# LED_V2_0.net
KiCad netlist of a schematic drawn in Altium Designer
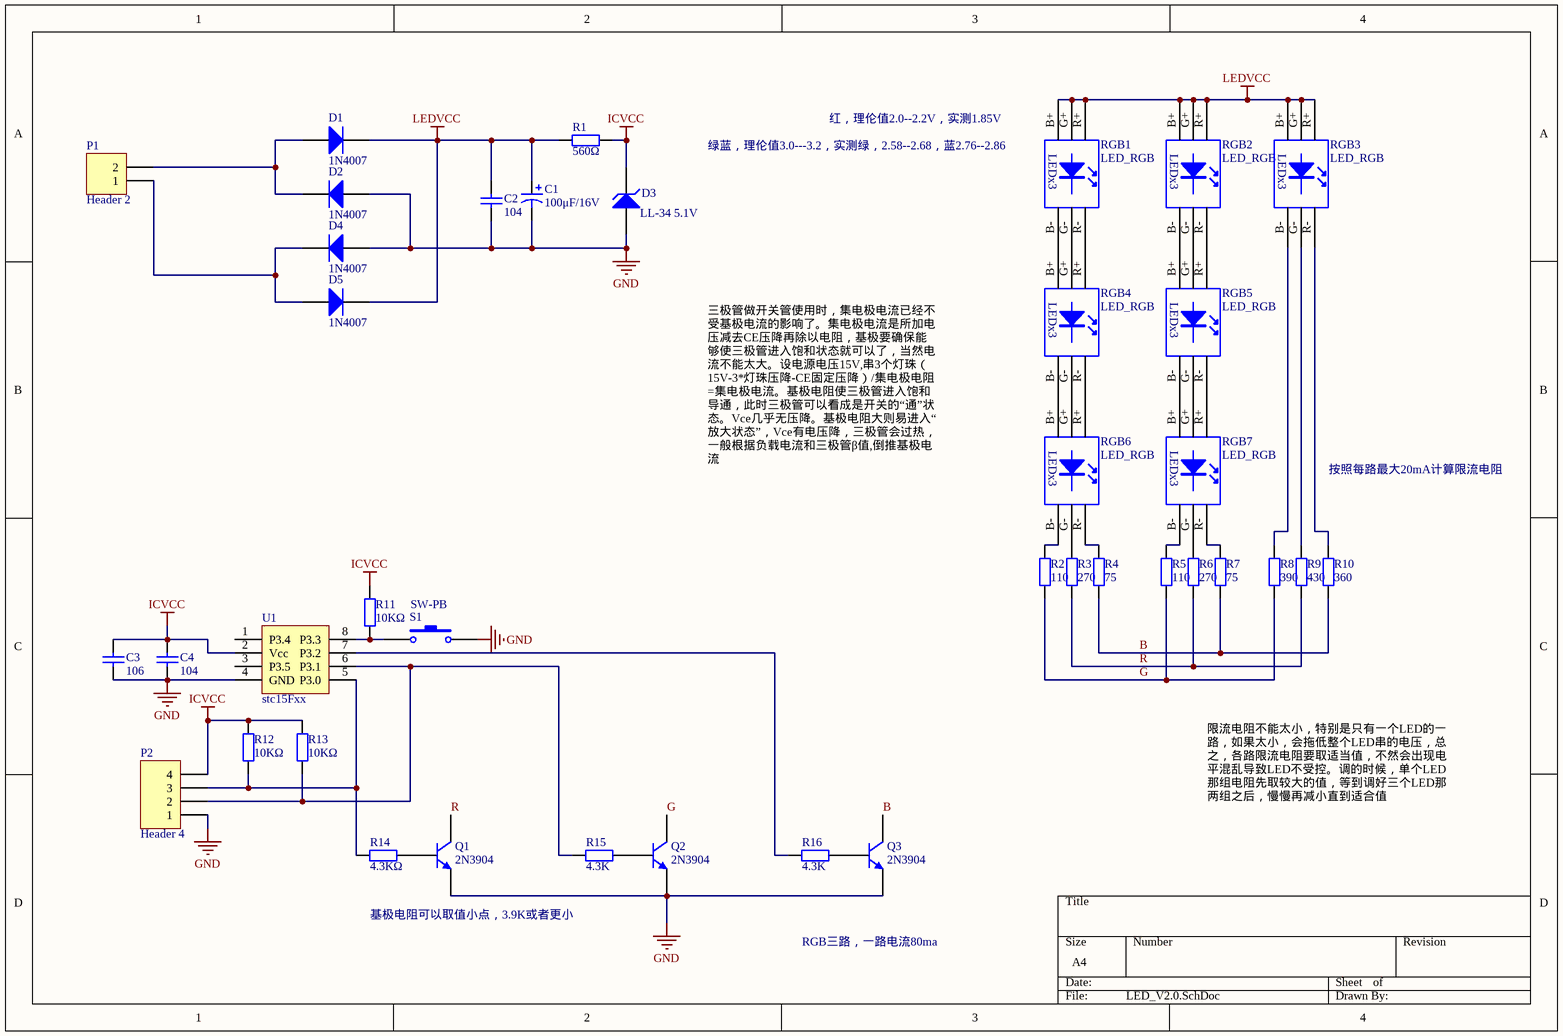
[diagram p0: LED_V2.0.SchDoc]

(export (version "E")
  (design (tool "Eeschema 10.0.6"))
  (components
    (comp (ref "C1")
      (value "100μF/16V")
      (footprint "CAP_D5")
      (description "Polarized Capacitor (Surface Mount)")
      (fields (field (name "PUBLISHER") "Altium Limited"))
      (libsource (lib "Miscellaneous Devices") (part "Cap Pol3"))
    )
    (comp (ref "C2")
      (value "104")
      (footprint "0805")
      (description "Capacitor")
      (fields (field (name "PUBLISHER") "Altium Limited"))
      (libsource (lib "Miscellaneous Devices") (part "Cap"))
    )
    (comp (ref "C3")
      (value "106")
      (footprint "0805")
      (description "Capacitor")
      (fields (field (name "PUBLISHER") "Altium Limited"))
      (libsource (lib "Miscellaneous Devices") (part "Cap"))
    )
    (comp (ref "C4")
      (value "104")
      (footprint "0805")
      (description "Capacitor")
      (fields (field (name "PUBLISHER") "Altium Limited"))
      (libsource (lib "Miscellaneous Devices") (part "Cap"))
    )
    (comp (ref "D1")
      (value "1N4007")
      (footprint "SMB_diode")
      (description "1 Amp General Purpose Rectifier")
      (fields (field (name "PUBLISHER") "Altium Limited"))
      (libsource (lib "Miscellaneous Devices") (part "Diode 1N4007"))
    )
    (comp (ref "D2")
      (value "1N4007")
      (footprint "SMB_diode")
      (description "1 Amp General Purpose Rectifier")
      (fields (field (name "PUBLISHER") "Altium Limited"))
      (libsource (lib "Miscellaneous Devices") (part "Diode 1N4007"))
    )
    (comp (ref "D3")
      (value "LL-34 5.1V")
      (footprint "SMB_diode")
      (description "Zener Diode")
      (fields (field (name "PUBLISHER") "Altium Limited"))
      (libsource (lib "Miscellaneous Devices") (part "D Zener"))
    )
    (comp (ref "D4")
      (value "1N4007")
      (footprint "SMB_diode")
      (description "1 Amp General Purpose Rectifier")
      (fields (field (name "PUBLISHER") "Altium Limited"))
      (libsource (lib "Miscellaneous Devices") (part "Diode 1N4007"))
    )
    (comp (ref "D5")
      (value "1N4007")
      (footprint "SMB_diode")
      (description "1 Amp General Purpose Rectifier")
      (fields (field (name "PUBLISHER") "Altium Limited"))
      (libsource (lib "Miscellaneous Devices") (part "Diode 1N4007"))
    )
    (comp (ref "P1")
      (value "Header 2")
      (footprint "CON_2PIN")
      (description "Header, 2-Pin")
      (fields (field (name "PUBLISHER") "Altium Limited"))
      (libsource (lib "Miscellaneous Connectors") (part "Header 2"))
    )
    (comp (ref "P2")
      (value "Header 4")
      (footprint "TESTPonit_4P")
      (description "Header, 4-Pin")
      (fields (field (name "PUBLISHER") "Altium Limited"))
      (libsource (lib "Miscellaneous Connectors") (part "Header 4"))
    )
    (comp (ref "Q1")
      (value "2N3904")
      (footprint "SOT_23")
      (description "NPN General Purpose Amplifier")
      (fields (field (name "PUBLISHER") "Altium Limited"))
      (libsource (lib "Miscellaneous Devices") (part "2N3904"))
    )
    (comp (ref "Q2")
      (value "2N3904")
      (footprint "SOT_23")
      (description "NPN General Purpose Amplifier")
      (fields (field (name "PUBLISHER") "Altium Limited"))
      (libsource (lib "Miscellaneous Devices") (part "2N3904"))
    )
    (comp (ref "Q3")
      (value "2N3904")
      (footprint "SOT_23")
      (description "NPN General Purpose Amplifier")
      (fields (field (name "PUBLISHER") "Altium Limited"))
      (libsource (lib "Miscellaneous Devices") (part "2N3904"))
    )
    (comp (ref "R1")
      (value "560Ω")
      (footprint "0805")
      (description "Resistor")
      (fields (field (name "PUBLISHER") "Altium Limited"))
      (libsource (lib "Miscellaneous Devices") (part "Res2"))
    )
    (comp (ref "R2")
      (value "110")
      (footprint "0805")
      (description "Resistor")
      (fields (field (name "PUBLISHER") "Altium Limited"))
      (libsource (lib "") (part "Res2_1"))
    )
    (comp (ref "R3")
      (value "270")
      (footprint "0805")
      (description "Resistor")
      (fields (field (name "PUBLISHER") "Altium Limited"))
      (libsource (lib "") (part "Res2_1"))
    )
    (comp (ref "R4")
      (value "75")
      (footprint "0805")
      (description "Resistor")
      (fields (field (name "PUBLISHER") "Altium Limited"))
      (libsource (lib "") (part "Res2_1"))
    )
    (comp (ref "R5")
      (value "110")
      (footprint "0805")
      (description "Resistor")
      (fields (field (name "PUBLISHER") "Altium Limited"))
      (libsource (lib "") (part "Res2_1"))
    )
    (comp (ref "R6")
      (value "270")
      (footprint "0805")
      (description "Resistor")
      (fields (field (name "PUBLISHER") "Altium Limited"))
      (libsource (lib "") (part "Res2_1"))
    )
    (comp (ref "R7")
      (value "75")
      (footprint "0805")
      (description "Resistor")
      (fields (field (name "PUBLISHER") "Altium Limited"))
      (libsource (lib "") (part "Res2_1"))
    )
    (comp (ref "R8")
      (value "390")
      (footprint "0805")
      (description "Resistor")
      (fields (field (name "PUBLISHER") "Altium Limited"))
      (libsource (lib "") (part "Res2_1"))
    )
    (comp (ref "R9")
      (value "430")
      (footprint "0805")
      (description "Resistor")
      (fields (field (name "PUBLISHER") "Altium Limited"))
      (libsource (lib "") (part "Res2_1"))
    )
    (comp (ref "R10")
      (value "360")
      (footprint "0805")
      (description "Resistor")
      (fields (field (name "PUBLISHER") "Altium Limited"))
      (libsource (lib "") (part "Res2_1"))
    )
    (comp (ref "R11")
      (value "10KΩ")
      (footprint "0805")
      (description "Resistor")
      (fields (field (name "PUBLISHER") "Altium Limited"))
      (libsource (lib "") (part "Res2_1"))
    )
    (comp (ref "R12")
      (value "10KΩ")
      (footprint "0805")
      (description "Resistor")
      (fields (field (name "PUBLISHER") "Altium Limited"))
      (libsource (lib "") (part "Res2_1"))
    )
    (comp (ref "R13")
      (value "10KΩ")
      (footprint "0805")
      (description "Resistor")
      (fields (field (name "PUBLISHER") "Altium Limited"))
      (libsource (lib "") (part "Res2_1"))
    )
    (comp (ref "R14")
      (value "4.3KΩ")
      (footprint "0805")
      (description "Resistor")
      (fields (field (name "PUBLISHER") "Altium Limited"))
      (libsource (lib "Miscellaneous Devices") (part "Res2"))
    )
    (comp (ref "R15")
      (value "4.3K")
      (footprint "0805")
      (description "Resistor")
      (fields (field (name "PUBLISHER") "Altium Limited"))
      (libsource (lib "Miscellaneous Devices") (part "Res2"))
    )
    (comp (ref "R16")
      (value "4.3K")
      (footprint "0805")
      (description "Resistor")
      (fields (field (name "PUBLISHER") "Altium Limited"))
      (libsource (lib "Miscellaneous Devices") (part "Res2"))
    )
    (comp (ref "RGB1") (value "LED_RGB") (footprint "RGB_5050") (libsource (lib "IUSED") (part "LED_RGB")))
    (comp (ref "RGB2") (value "LED_RGB") (footprint "RGB_5050") (libsource (lib "IUSED") (part "LED_RGB")))
    (comp (ref "RGB3") (value "LED_RGB") (footprint "RGB_5050") (libsource (lib "IUSED") (part "LED_RGB")))
    (comp (ref "RGB4") (value "LED_RGB") (footprint "RGB_5050") (libsource (lib "IUSED") (part "LED_RGB")))
    (comp (ref "RGB5") (value "LED_RGB") (footprint "RGB_5050") (libsource (lib "IUSED") (part "LED_RGB")))
    (comp (ref "RGB6") (value "LED_RGB") (footprint "RGB_5050") (libsource (lib "IUSED") (part "LED_RGB")))
    (comp (ref "RGB7") (value "LED_RGB") (footprint "RGB_5050") (libsource (lib "IUSED") (part "LED_RGB")))
    (comp (ref "S1")
      (value "SW-PB")
      (footprint "SW_2")
      (description "Switch")
      (fields (field (name "PUBLISHER") "Altium Limited"))
      (libsource (lib "常用器件") (part "SW-PB"))
    )
    (comp (ref "U1") (value "stc15Fxx") (footprint "SOP_8") (libsource (lib "IUSED") (part "stc15Fxx")))
  )
  (nets
    (net (code "1") (name "/B") (class "Default")
      (node (ref "Q3") (pin "3") (pinfunction "C_3") (pintype "passive"))
      (node (ref "R10") (pin "1") (pinfunction "1_1") (pintype "passive"))
      (node (ref "R4") (pin "1") (pinfunction "1_1") (pintype "passive"))
      (node (ref "R7") (pin "1") (pinfunction "1_1") (pintype "passive"))
    )
    (net (code "2") (name "/G") (class "Default")
      (node (ref "Q2") (pin "3") (pinfunction "C_3") (pintype "passive"))
      (node (ref "R2") (pin "1") (pinfunction "1_1") (pintype "passive"))
      (node (ref "R5") (pin "1") (pinfunction "1_1") (pintype "passive"))
      (node (ref "R8") (pin "1") (pinfunction "1_1") (pintype "passive"))
    )
    (net (code "3") (name "/R") (class "Default")
      (node (ref "Q1") (pin "3") (pinfunction "C_3") (pintype "passive"))
      (node (ref "R3") (pin "1") (pinfunction "1_1") (pintype "passive"))
      (node (ref "R6") (pin "1") (pinfunction "1_1") (pintype "passive"))
      (node (ref "R9") (pin "1") (pinfunction "1_1") (pintype "passive"))
    )
    (net (code "4") (name "GND") (class "Default")
      (node (ref "C1") (pin "2") (pinfunction "2_2") (pintype "passive"))
      (node (ref "C2") (pin "1") (pinfunction "1_1") (pintype "passive"))
      (node (ref "C3") (pin "1") (pinfunction "1_1") (pintype "passive"))
      (node (ref "C4") (pin "1") (pinfunction "1_1") (pintype "passive"))
      (node (ref "D2") (pin "1") (pinfunction "A_1") (pintype "passive"))
      (node (ref "D3") (pin "1") (pinfunction "A_1") (pintype "passive"))
      (node (ref "D4") (pin "1") (pinfunction "A_1") (pintype "passive"))
      (node (ref "P2") (pin "1") (pinfunction "1_1") (pintype "passive"))
      (node (ref "Q1") (pin "1") (pinfunction "E_1") (pintype "passive"))
      (node (ref "Q2") (pin "1") (pinfunction "E_1") (pintype "passive"))
      (node (ref "Q3") (pin "1") (pinfunction "E_1") (pintype "passive"))
      (node (ref "S1") (pin "2") (pinfunction "2_2") (pintype "passive"))
      (node (ref "U1") (pin "4") (pinfunction "GND_4") (pintype "passive"))
    )
    (net (code "5") (name "ICVCC") (class "Default")
      (node (ref "C3") (pin "2") (pinfunction "2_2") (pintype "passive"))
      (node (ref "C4") (pin "2") (pinfunction "2_2") (pintype "passive"))
      (node (ref "D3") (pin "2") (pinfunction "K_2") (pintype "passive"))
      (node (ref "P2") (pin "4") (pinfunction "4_4") (pintype "passive"))
      (node (ref "R1") (pin "2") (pinfunction "2_2") (pintype "passive"))
      (node (ref "R11") (pin "2") (pinfunction "2_2") (pintype "passive"))
      (node (ref "R12") (pin "2") (pinfunction "2_2") (pintype "passive"))
      (node (ref "R13") (pin "2") (pinfunction "2_2") (pintype "passive"))
      (node (ref "U1") (pin "2") (pinfunction "Vcc_2") (pintype "passive"))
    )
    (net (code "6") (name "LEDVCC") (class "Default")
      (node (ref "C1") (pin "1") (pinfunction "1_1") (pintype "passive"))
      (node (ref "C2") (pin "2") (pinfunction "2_2") (pintype "passive"))
      (node (ref "D1") (pin "2") (pinfunction "K_2") (pintype "passive"))
      (node (ref "D5") (pin "2") (pinfunction "K_2") (pintype "passive"))
      (node (ref "R1") (pin "1") (pinfunction "1_1") (pintype "passive"))
      (node (ref "RGB1") (pin "B+") (pinfunction "3_B+") (pintype "passive"))
      (node (ref "RGB1") (pin "G+") (pinfunction "2_G+") (pintype "passive"))
      (node (ref "RGB1") (pin "R+") (pinfunction "1_R+") (pintype "passive"))
      (node (ref "RGB2") (pin "B+") (pinfunction "3_B+") (pintype "passive"))
      (node (ref "RGB2") (pin "G+") (pinfunction "2_G+") (pintype "passive"))
      (node (ref "RGB2") (pin "R+") (pinfunction "1_R+") (pintype "passive"))
      (node (ref "RGB3") (pin "B+") (pinfunction "3_B+") (pintype "passive"))
      (node (ref "RGB3") (pin "G+") (pinfunction "2_G+") (pintype "passive"))
      (node (ref "RGB3") (pin "R+") (pinfunction "1_R+") (pintype "passive"))
    )
    (net (code "7") (name "Net-(D1-A)") (class "Default")
      (node (ref "D1") (pin "1") (pinfunction "A_1") (pintype "passive"))
      (node (ref "D2") (pin "2") (pinfunction "K_2") (pintype "passive"))
      (node (ref "P1") (pin "2") (pinfunction "2_2") (pintype "passive"))
    )
    (net (code "8") (name "Net-(D4-K)") (class "Default")
      (node (ref "D4") (pin "2") (pinfunction "K_2") (pintype "passive"))
      (node (ref "D5") (pin "1") (pinfunction "A_1") (pintype "passive"))
      (node (ref "P1") (pin "1") (pinfunction "1_1") (pintype "passive"))
    )
    (net (code "9") (name "Net-(Q1-B)") (class "Default")
      (node (ref "Q1") (pin "2") (pinfunction "B_2") (pintype "passive"))
      (node (ref "R14") (pin "2") (pinfunction "2_2") (pintype "passive"))
    )
    (net (code "10") (name "Net-(Q2-B)") (class "Default")
      (node (ref "Q2") (pin "2") (pinfunction "B_2") (pintype "passive"))
      (node (ref "R15") (pin "2") (pinfunction "2_2") (pintype "passive"))
    )
    (net (code "11") (name "Net-(Q3-B)") (class "Default")
      (node (ref "Q3") (pin "2") (pinfunction "B_2") (pintype "passive"))
      (node (ref "R16") (pin "2") (pinfunction "2_2") (pintype "passive"))
    )
    (net (code "12") (name "Net-(RGB1-4)") (class "Default")
      (node (ref "RGB1") (pin "R-") (pinfunction "4_R-") (pintype "passive"))
      (node (ref "RGB4") (pin "R+") (pinfunction "1_R+") (pintype "passive"))
    )
    (net (code "13") (name "Net-(RGB1-5)") (class "Default")
      (node (ref "RGB1") (pin "G-") (pinfunction "5_G-") (pintype "passive"))
      (node (ref "RGB4") (pin "G+") (pinfunction "2_G+") (pintype "passive"))
    )
    (net (code "14") (name "Net-(RGB1-6)") (class "Default")
      (node (ref "RGB1") (pin "B-") (pinfunction "6_B-") (pintype "passive"))
      (node (ref "RGB4") (pin "B+") (pinfunction "3_B+") (pintype "passive"))
    )
    (net (code "15") (name "Net-(RGB2-4)") (class "Default")
      (node (ref "RGB2") (pin "R-") (pinfunction "4_R-") (pintype "passive"))
      (node (ref "RGB5") (pin "R+") (pinfunction "1_R+") (pintype "passive"))
    )
    (net (code "16") (name "Net-(RGB2-5)") (class "Default")
      (node (ref "RGB2") (pin "G-") (pinfunction "5_G-") (pintype "passive"))
      (node (ref "RGB5") (pin "G+") (pinfunction "2_G+") (pintype "passive"))
    )
    (net (code "17") (name "Net-(RGB2-6)") (class "Default")
      (node (ref "RGB2") (pin "B-") (pinfunction "6_B-") (pintype "passive"))
      (node (ref "RGB5") (pin "B+") (pinfunction "3_B+") (pintype "passive"))
    )
    (net (code "18") (name "Net-(RGB3-4)") (class "Default")
      (node (ref "R10") (pin "2") (pinfunction "2_2") (pintype "passive"))
      (node (ref "RGB3") (pin "R-") (pinfunction "4_R-") (pintype "passive"))
    )
    (net (code "19") (name "Net-(RGB3-5)") (class "Default")
      (node (ref "R9") (pin "2") (pinfunction "2_2") (pintype "passive"))
      (node (ref "RGB3") (pin "G-") (pinfunction "5_G-") (pintype "passive"))
    )
    (net (code "20") (name "Net-(RGB3-6)") (class "Default")
      (node (ref "R8") (pin "2") (pinfunction "2_2") (pintype "passive"))
      (node (ref "RGB3") (pin "B-") (pinfunction "6_B-") (pintype "passive"))
    )
    (net (code "21") (name "Net-(RGB4-4)") (class "Default")
      (node (ref "RGB4") (pin "R-") (pinfunction "4_R-") (pintype "passive"))
      (node (ref "RGB6") (pin "R+") (pinfunction "1_R+") (pintype "passive"))
    )
    (net (code "22") (name "Net-(RGB4-5)") (class "Default")
      (node (ref "RGB4") (pin "G-") (pinfunction "5_G-") (pintype "passive"))
      (node (ref "RGB6") (pin "G+") (pinfunction "2_G+") (pintype "passive"))
    )
    (net (code "23") (name "Net-(RGB4-6)") (class "Default")
      (node (ref "RGB4") (pin "B-") (pinfunction "6_B-") (pintype "passive"))
      (node (ref "RGB6") (pin "B+") (pinfunction "3_B+") (pintype "passive"))
    )
    (net (code "24") (name "Net-(RGB5-4)") (class "Default")
      (node (ref "RGB5") (pin "R-") (pinfunction "4_R-") (pintype "passive"))
      (node (ref "RGB7") (pin "R+") (pinfunction "1_R+") (pintype "passive"))
    )
    (net (code "25") (name "Net-(RGB5-5)") (class "Default")
      (node (ref "RGB5") (pin "G-") (pinfunction "5_G-") (pintype "passive"))
      (node (ref "RGB7") (pin "G+") (pinfunction "2_G+") (pintype "passive"))
    )
    (net (code "26") (name "Net-(RGB5-6)") (class "Default")
      (node (ref "RGB5") (pin "B-") (pinfunction "6_B-") (pintype "passive"))
      (node (ref "RGB7") (pin "B+") (pinfunction "3_B+") (pintype "passive"))
    )
    (net (code "27") (name "Net-(RGB6-4)") (class "Default")
      (node (ref "R4") (pin "2") (pinfunction "2_2") (pintype "passive"))
      (node (ref "RGB6") (pin "R-") (pinfunction "4_R-") (pintype "passive"))
    )
    (net (code "28") (name "Net-(RGB6-5)") (class "Default")
      (node (ref "R3") (pin "2") (pinfunction "2_2") (pintype "passive"))
      (node (ref "RGB6") (pin "G-") (pinfunction "5_G-") (pintype "passive"))
    )
    (net (code "29") (name "Net-(RGB6-6)") (class "Default")
      (node (ref "R2") (pin "2") (pinfunction "2_2") (pintype "passive"))
      (node (ref "RGB6") (pin "B-") (pinfunction "6_B-") (pintype "passive"))
    )
    (net (code "30") (name "Net-(RGB7-4)") (class "Default")
      (node (ref "R7") (pin "2") (pinfunction "2_2") (pintype "passive"))
      (node (ref "RGB7") (pin "R-") (pinfunction "4_R-") (pintype "passive"))
    )
    (net (code "31") (name "Net-(RGB7-5)") (class "Default")
      (node (ref "R6") (pin "2") (pinfunction "2_2") (pintype "passive"))
      (node (ref "RGB7") (pin "G-") (pinfunction "5_G-") (pintype "passive"))
    )
    (net (code "32") (name "Net-(RGB7-6)") (class "Default")
      (node (ref "R5") (pin "2") (pinfunction "2_2") (pintype "passive"))
      (node (ref "RGB7") (pin "B-") (pinfunction "6_B-") (pintype "passive"))
    )
    (net (code "33") (name "Net-(U1-P3.0)") (class "Default")
      (node (ref "P2") (pin "3") (pinfunction "3_3") (pintype "passive"))
      (node (ref "R12") (pin "1") (pinfunction "1_1") (pintype "passive"))
      (node (ref "R14") (pin "1") (pinfunction "1_1") (pintype "passive"))
      (node (ref "U1") (pin "5") (pinfunction "P3.0_5") (pintype "passive"))
    )
    (net (code "34") (name "Net-(U1-P3.1)") (class "Default")
      (node (ref "P2") (pin "2") (pinfunction "2_2") (pintype "passive"))
      (node (ref "R13") (pin "1") (pinfunction "1_1") (pintype "passive"))
      (node (ref "R15") (pin "1") (pinfunction "1_1") (pintype "passive"))
      (node (ref "U1") (pin "6") (pinfunction "P3.1_6") (pintype "passive"))
    )
    (net (code "35") (name "Net-(U1-P3.2)") (class "Default")
      (node (ref "R16") (pin "1") (pinfunction "1_1") (pintype "passive"))
      (node (ref "U1") (pin "7") (pinfunction "P3.2_7") (pintype "passive"))
    )
    (net (code "36") (name "Net-(U1-P3.3)") (class "Default")
      (node (ref "R11") (pin "1") (pinfunction "1_1") (pintype "passive"))
      (node (ref "S1") (pin "1") (pinfunction "1_1") (pintype "passive"))
      (node (ref "U1") (pin "8") (pinfunction "P3.3_8") (pintype "passive"))
    )
    (net (code "37") (name "unconnected-(U1-P3.4-Pad1)") (class "Default")
      (node (ref "U1") (pin "1") (pinfunction "P3.4_1") (pintype "passive"))
    )
    (net (code "38") (name "unconnected-(U1-P3.5-Pad3)") (class "Default")
      (node (ref "U1") (pin "3") (pinfunction "P3.5_3") (pintype "passive"))
    )
  )
)
